# Sheet1.net
KiCad netlist of a schematic drawn in Altium Designer
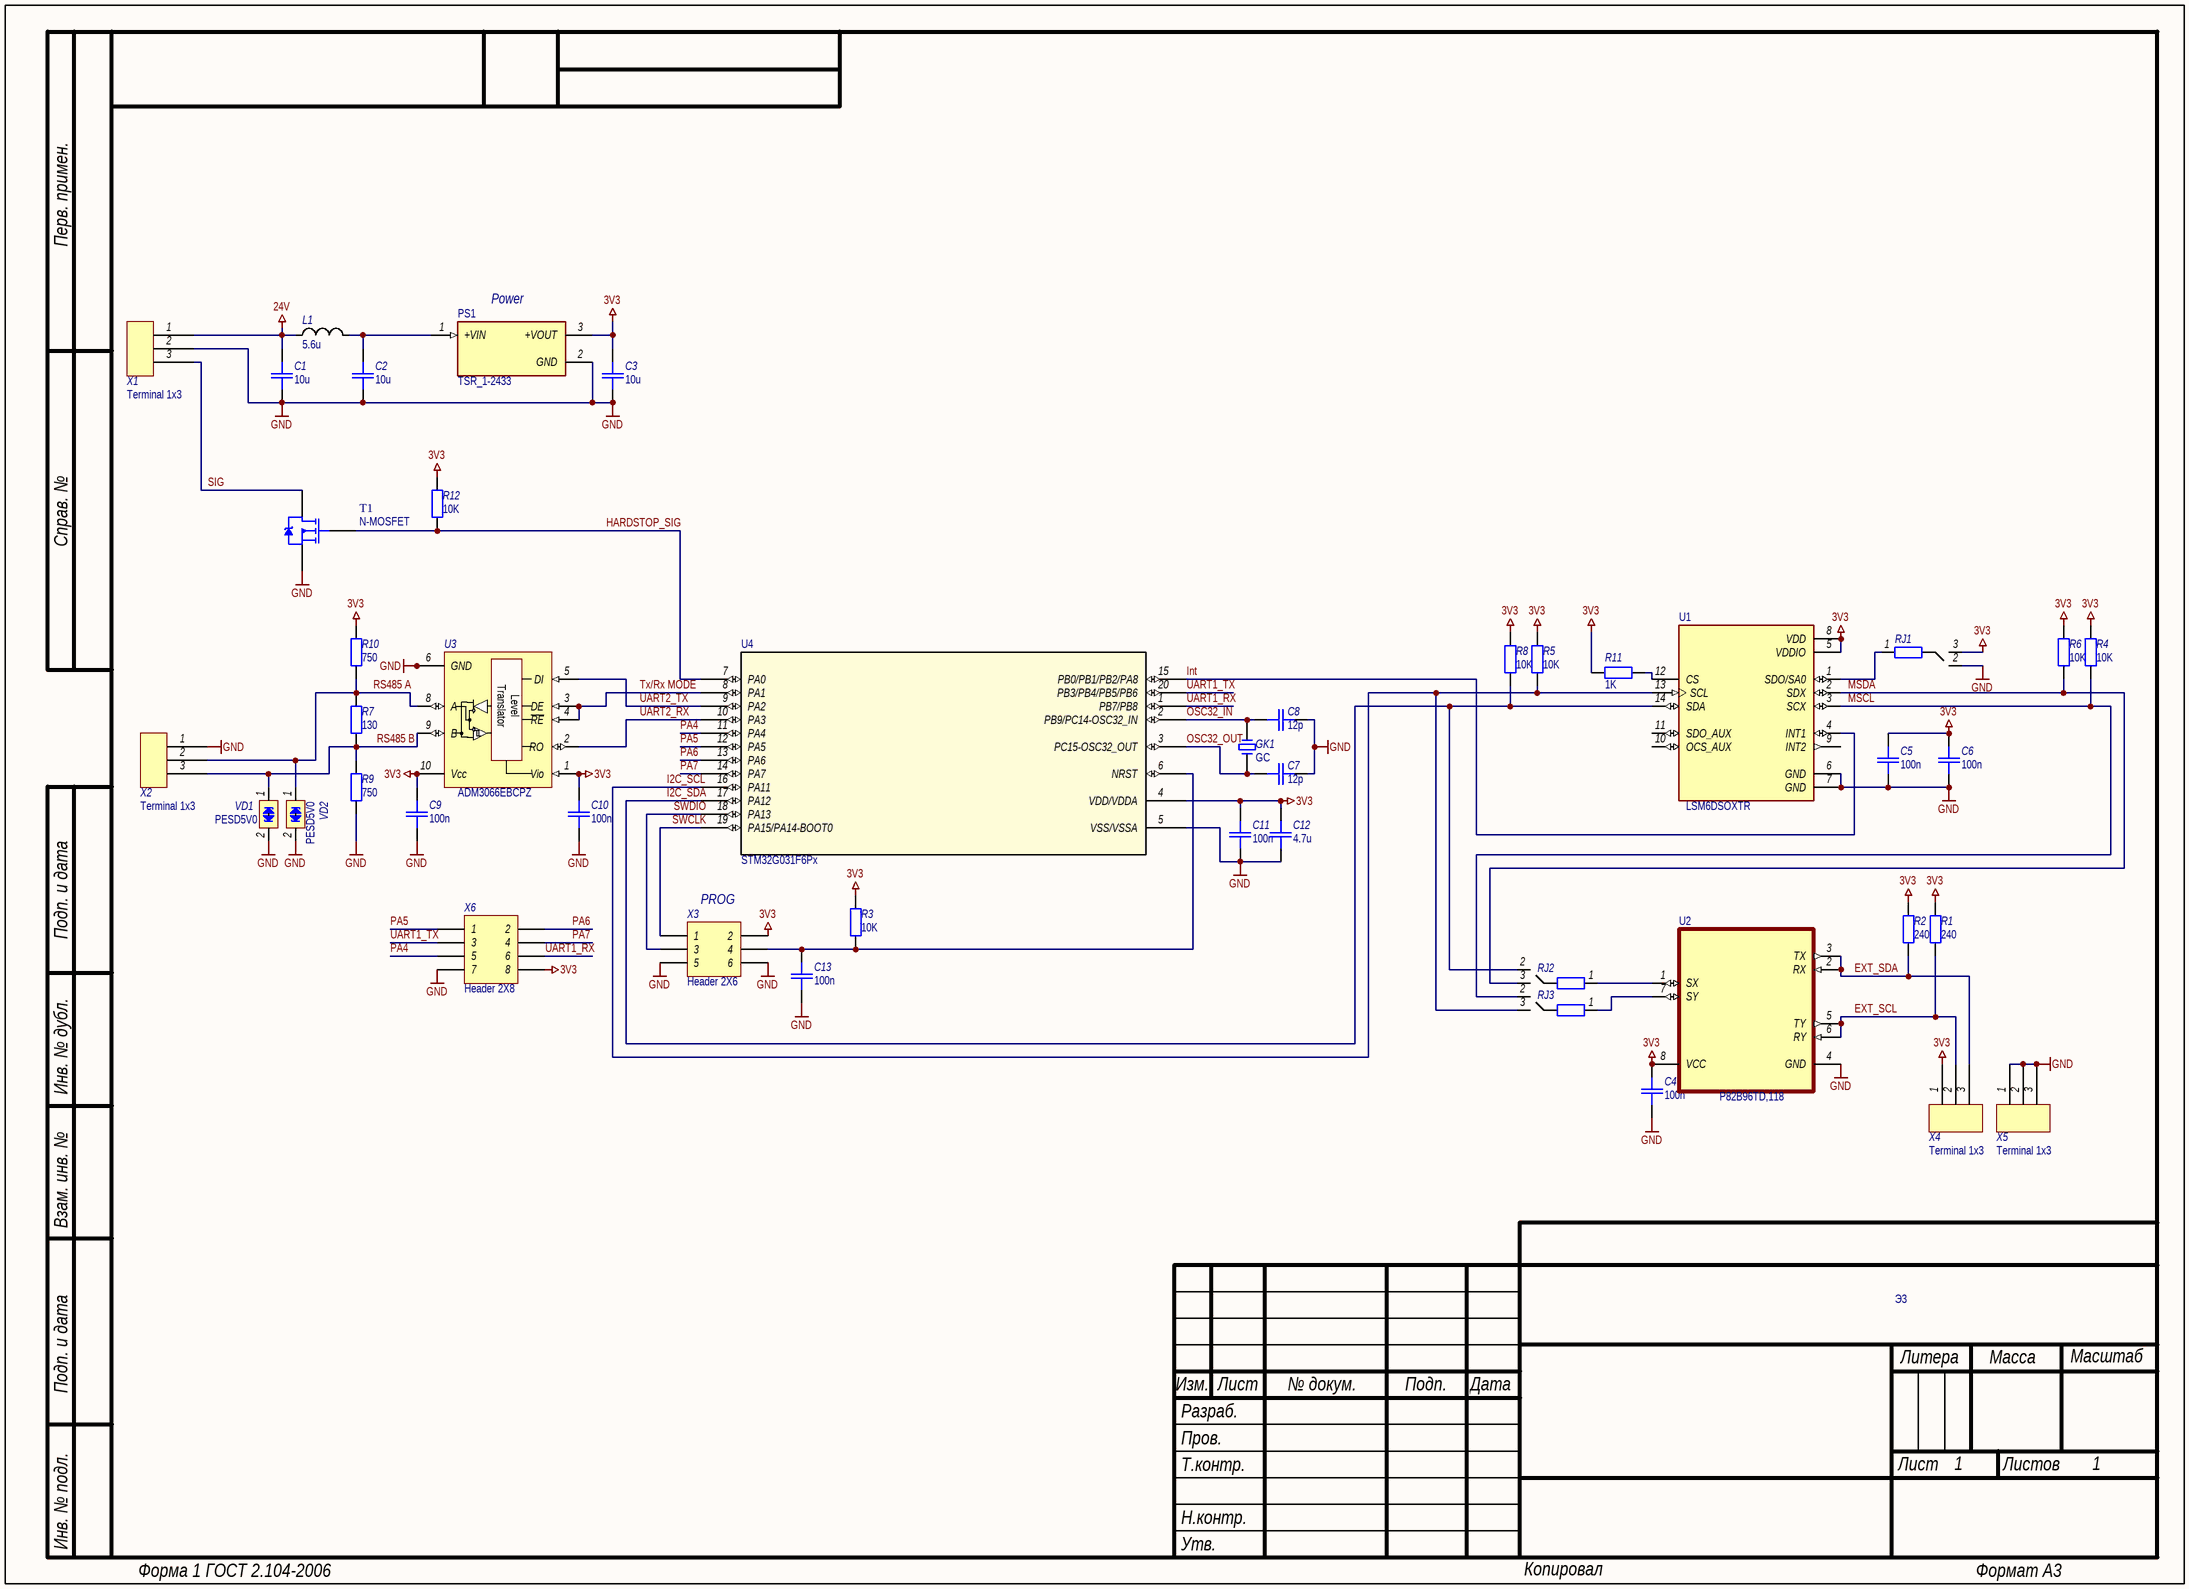
[diagram p0: Sheet1.SchDoc]

(export (version "E")
  (design (tool "Eeschema 10.0.6"))
  (components
    (comp (ref "C1")
      (value "10u")
      (footprint "SMD_C0805")
      (description "Capacitor")
      (fields (field (name "Comment") "K10-79"))
      (libsource (lib "Capacitor") (part "Capacitor"))
    )
    (comp (ref "C2")
      (value "10u")
      (footprint "SMD_C0805")
      (description "Capacitor")
      (fields (field (name "Comment") "K10-79"))
      (libsource (lib "Capacitor") (part "Capacitor"))
    )
    (comp (ref "C3")
      (value "10u")
      (footprint "SMD_C0805")
      (description "Capacitor")
      (fields (field (name "Comment") "K10-79"))
      (libsource (lib "Capacitor") (part "Capacitor"))
    )
    (comp (ref "C4")
      (value "100n")
      (footprint "SMD_C0805")
      (description "Capacitor")
      (fields (field (name "Comment") "K10-79"))
      (libsource (lib "Capacitor") (part "Capacitor"))
    )
    (comp (ref "C5")
      (value "100n")
      (footprint "SMD_C0805")
      (description "Capacitor")
      (fields (field (name "Comment") "K10-79"))
      (libsource (lib "Capacitor") (part "Capacitor"))
    )
    (comp (ref "C6")
      (value "100n")
      (footprint "SMD_C0805")
      (description "Capacitor")
      (fields (field (name "Comment") "K10-79"))
      (libsource (lib "Capacitor") (part "Capacitor"))
    )
    (comp (ref "C7")
      (value "12p")
      (footprint "SMD_C0805")
      (description "Capacitor")
      (fields (field (name "Comment") "K10-79"))
      (libsource (lib "Capacitor") (part "Capacitor"))
    )
    (comp (ref "C8")
      (value "12p")
      (footprint "SMD_C0805")
      (description "Capacitor")
      (fields (field (name "Comment") "K10-79"))
      (libsource (lib "Capacitor") (part "Capacitor"))
    )
    (comp (ref "C9")
      (value "100n")
      (footprint "SMD_C0805")
      (description "Capacitor")
      (fields (field (name "Comment") "K10-79"))
      (libsource (lib "Capacitor") (part "Capacitor"))
    )
    (comp (ref "C10")
      (value "100n")
      (footprint "SMD_C0805")
      (description "Capacitor")
      (fields (field (name "Comment") "K10-79"))
      (libsource (lib "Capacitor") (part "Capacitor"))
    )
    (comp (ref "C11")
      (value "100n")
      (footprint "SMD_C0805")
      (description "Capacitor")
      (fields (field (name "Comment") "K10-79"))
      (libsource (lib "Capacitor") (part "Capacitor"))
    )
    (comp (ref "C12")
      (value "4.7u")
      (footprint "SMD_C0805")
      (description "Capacitor")
      (fields (field (name "Comment") "K10-79"))
      (libsource (lib "Capacitor") (part "Capacitor"))
    )
    (comp (ref "C13")
      (value "100n")
      (footprint "SMD_C0805")
      (description "Capacitor")
      (fields (field (name "Comment") "K10-79"))
      (libsource (lib "Capacitor") (part "Capacitor"))
    )
    (comp (ref "GK1")
      (value "32.768k")
      (footprint "DT-38T")
      (description "Generic 2-Pin Crystal Oscillator")
      (fields (field (name "НАИМЕНОВАНИЕ") "GC"))
      (libsource (lib "Oscillator") (part "Crystal_Generic"))
    )
    (comp (ref "L1")
      (value "5.6u")
      (footprint "SMD_0805")
      (description "Inductor")
      (libsource (lib "Inductor") (part "Inductor"))
    )
    (comp (ref "PS1")
      (value "TSR_1-2433")
      (footprint "CONV_TSR_1-2433")
      (description "1 Amp POL switching regulator, 4.6 to -36 VDC input, pos.-pos. circuit, LM78 compatible, SIP-3")
      (fields (field (name "MP") "TSR 1-2433") (field (name "MF") "Traco Power"))
      (libsource (lib "TSR_1-2433") (part "TSR_1-2433"))
    )
    (comp (ref "R1")
      (value "240")
      (footprint "SMD_0805")
      (description "Resistor")
      (fields (field (name "Comment") "OSM R1-8"))
      (libsource (lib "Resistor") (part "Resistor"))
    )
    (comp (ref "R2")
      (value "240")
      (footprint "SMD_0805")
      (description "Resistor")
      (fields (field (name "Comment") "OSM R1-8"))
      (libsource (lib "Resistor") (part "Resistor"))
    )
    (comp (ref "R3")
      (value "10K")
      (footprint "SMD_0805")
      (description "Resistor")
      (fields (field (name "Comment") "OSM R1-8"))
      (libsource (lib "Resistor") (part "Resistor"))
    )
    (comp (ref "R4")
      (value "10K")
      (footprint "SMD_0805")
      (description "Resistor")
      (fields (field (name "Comment") "OSM R1-8"))
      (libsource (lib "Resistor") (part "Resistor"))
    )
    (comp (ref "R5")
      (value "10K")
      (footprint "SMD_0805")
      (description "Resistor")
      (fields (field (name "Comment") "OSM R1-8"))
      (libsource (lib "Resistor") (part "Resistor"))
    )
    (comp (ref "R6")
      (value "10K")
      (footprint "SMD_0805")
      (description "Resistor")
      (fields (field (name "Comment") "OSM R1-8"))
      (libsource (lib "Resistor") (part "Resistor"))
    )
    (comp (ref "R7")
      (value "130")
      (footprint "SMD_0805")
      (description "Resistor")
      (fields (field (name "Comment") "OSM R1-8"))
      (libsource (lib "") (part "Resistor_2"))
    )
    (comp (ref "R8")
      (value "10K")
      (footprint "SMD_0805")
      (description "Resistor")
      (fields (field (name "Comment") "OSM R1-8"))
      (libsource (lib "Resistor") (part "Resistor"))
    )
    (comp (ref "R9")
      (value "750")
      (footprint "SMD_0805")
      (description "Resistor")
      (fields (field (name "Comment") "OSM R1-8"))
      (libsource (lib "Resistor") (part "Resistor"))
    )
    (comp (ref "R10")
      (value "750")
      (footprint "SMD_0805")
      (description "Resistor")
      (fields (field (name "Comment") "OSM R1-8"))
      (libsource (lib "") (part "Resistor_2"))
    )
    (comp (ref "R11")
      (value "1K")
      (footprint "SMD_0805")
      (description "Resistor")
      (fields (field (name "Comment") "OSM R1-8"))
      (libsource (lib "") (part "Resistor_1"))
    )
    (comp (ref "R12")
      (value "10K")
      (footprint "SMD_0805")
      (description "Resistor")
      (fields (field (name "Comment") "OSM R1-8"))
      (libsource (lib "") (part "Resistor_2"))
    )
    (comp (ref "RJ1")
      (value "OSM R1-8")
      (footprint "SMD_JMP_0805")
      (description "Resistor-Jumper")
      (libsource (lib "Passive") (part "Resistor_Jamper"))
    )
    (comp (ref "RJ2")
      (value "OSM R1-8")
      (footprint "SMD_JMP_0805")
      (description "Resistor-Jumper")
      (libsource (lib "") (part "Resistor_Jamper_1"))
    )
    (comp (ref "RJ3")
      (value "OSM R1-8")
      (footprint "SMD_JMP_0805")
      (description "Resistor-Jumper")
      (libsource (lib "") (part "Resistor_Jamper_1"))
    )
    (comp (ref "T1")
      (value "N-MOSFET")
      (footprint "SOT-23")
      (description "N channel Generic MosFET")
      (fields (field (name "НАИМЕНОВАНИЕ") "N-MOSFET"))
      (libsource (lib "Transistor") (part "N-MOSFET"))
    )
    (comp (ref "U1")
      (value "LSM6DSOXTR")
      (footprint "PQFN50P250X300X86-14N")
      (description "Accelerometer, Gyroscope, 6 Axis Sensor IÂ²C, SPI Output")
      (fields (field (name "MF") "STMicroelectronics"))
      (libsource (lib "LSM6DSOXTR") (part "LSM6DSOXTR"))
    )
    (comp (ref "U2")
      (value "P82B96TD,118")
      (footprint "SOIC127P600X175-8N")
      (description "Dual bidirectional bus buffer")
      (fields (field (name "MP") "P82B96TD-118"))
      (libsource (lib "P82B96TD_118") (part "P82B96TD,118"))
    )
    (comp (ref "U3")
      (value "ADM3066EBCPZ")
      (footprint "LFCSP-10_3x3")
      (description "3.0 V to 5.5 V, ±12 kV IEC ESD Protected, 500 kbps/50 Mbps RS-485 Transceiver")
      (libsource (lib "Transceiver") (part "ADM3066E"))
    )
    (comp (ref "U4")
      (value "STM32G031F6Px")
      (footprint "TSSOP20")
      (fields
        (field (name "MANUFACTURER_PART_NUMBER") "stm32g0_tssop20_t1")
        (field (name "COPYRIGHT") "Copyright (C) 2018 Accelerated Designs. All rights reserved")
      )
      (libsource (lib "ST Microelectronics STM32 G0") (part "STM32G031F6Px"))
    )
    (comp (ref "VD1")
      (value "PESD5V0")
      (footprint "SOD-323")
      (description "Low capacitance bidirectional ESD protection diodes")
      (libsource (lib "Diod") (part "PESDxL1BA"))
    )
    (comp (ref "VD2")
      (value "PESD5V0")
      (footprint "SOD-323")
      (description "Low capacitance bidirectional ESD protection diodes")
      (libsource (lib "Diod") (part "PESDxL1BA"))
    )
    (comp (ref "X1")
      (value "Terminal 1x3")
      (footprint "DXMG-3WAY")
      (libsource (lib "") (part "Terminal 1x3_1"))
    )
    (comp (ref "X2")
      (value "Terminal 1x3")
      (footprint "DXMG-3WAY")
      (libsource (lib "") (part "Terminal 1x3_1"))
    )
    (comp (ref "X3")
      (value "Header 2X6")
      (footprint "PLD2-6")
      (description "Header, 6-Pin, Dual row")
      (fields (field (name "НАИМЕНОВАНИЕ") "Header 2X6"))
      (libsource (lib "Connector") (part "Header 2X6"))
    )
    (comp (ref "X4")
      (value "Terminal 1x3")
      (footprint "DxMG 3WAY:DXMG-3WAY")
      (libsource (lib "DxMG 3WAY") (part "Terminal 1x3"))
    )
    (comp (ref "X5")
      (value "Terminal 1x3")
      (footprint "DxMG 3WAY:DXMG-3WAY")
      (libsource (lib "DxMG 3WAY") (part "Terminal 1x3"))
    )
    (comp (ref "X6")
      (value "Header 2X8")
      (footprint "PBD-8")
      (description "Header, 8-Pin, Dual row")
      (fields (field (name "НАИМЕНОВАНИЕ") "Header 2X8"))
      (libsource (lib "Connector") (part "Header 2X8"))
    )
  )
  (nets
    (net (code "1") (name "/EXT_SCL") (class "Default")
      (node (ref "R1") (pin "1") (pinfunction "1_1") (pintype "passive"))
      (node (ref "U2") (pin "5") (pinfunction "TY_5") (pintype "output"))
      (node (ref "U2") (pin "6") (pinfunction "RY_6") (pintype "input"))
      (node (ref "X4") (pin "2") (pinfunction "2_2") (pintype "passive"))
    )
    (net (code "2") (name "/EXT_SDA") (class "Default")
      (node (ref "R2") (pin "1") (pinfunction "1_1") (pintype "passive"))
      (node (ref "U2") (pin "2") (pinfunction "RX_2") (pintype "input"))
      (node (ref "U2") (pin "3") (pinfunction "TX_3") (pintype "output"))
      (node (ref "X4") (pin "3") (pinfunction "3_3") (pintype "passive"))
    )
    (net (code "3") (name "/HARDSTOP_SIG") (class "Default")
      (node (ref "R12") (pin "2") (pinfunction "2_2") (pintype "passive"))
      (node (ref "T1") (pin "G") (pinfunction "GATE_G") (pintype "passive"))
      (node (ref "U4") (pin "7") (pinfunction "PA0_7") (pintype "bidirectional"))
    )
    (net (code "4") (name "/I2C_SCL") (class "Default")
      (node (ref "R5") (pin "1") (pinfunction "1_1") (pintype "passive"))
      (node (ref "RJ3") (pin "3") (pintype "passive"))
      (node (ref "U1") (pin "13") (pinfunction "SCL_13") (pintype "input"))
      (node (ref "U4") (pin "16") (pinfunction "PA11_16") (pintype "bidirectional"))
    )
    (net (code "5") (name "/I2C_SDA") (class "Default")
      (node (ref "R8") (pin "1") (pinfunction "1_1") (pintype "passive"))
      (node (ref "RJ2") (pin "2") (pintype "passive"))
      (node (ref "U1") (pin "14") (pinfunction "SDA_14") (pintype "bidirectional"))
      (node (ref "U4") (pin "17") (pinfunction "PA12_17") (pintype "bidirectional"))
    )
    (net (code "6") (name "/Int") (class "Default")
      (node (ref "U1") (pin "4") (pinfunction "INT1_4") (pintype "bidirectional"))
      (node (ref "U4") (pin "15") (pinfunction "PB0/PB1/PB2/PA8_15") (pintype "bidirectional"))
    )
    (net (code "7") (name "/MSCL") (class "Default")
      (node (ref "R4") (pin "1") (pinfunction "1_1") (pintype "passive"))
      (node (ref "RJ3") (pin "2") (pintype "passive"))
      (node (ref "U1") (pin "3") (pinfunction "SCX_3") (pintype "bidirectional"))
    )
    (net (code "8") (name "/MSDA") (class "Default")
      (node (ref "R6") (pin "1") (pinfunction "1_1") (pintype "passive"))
      (node (ref "RJ2") (pin "3") (pintype "passive"))
      (node (ref "U1") (pin "2") (pinfunction "SDX_2") (pintype "bidirectional"))
    )
    (net (code "9") (name "/OSC32_IN") (class "Default")
      (node (ref "C8") (pin "2") (pinfunction "2_2") (pintype "passive"))
      (node (ref "GK1") (pin "1") (pinfunction "1_1") (pintype "passive"))
      (node (ref "U4") (pin "2") (pinfunction "PB9/PC14-OSC32_IN_2") (pintype "bidirectional"))
    )
    (net (code "10") (name "/OSC32_OUT") (class "Default")
      (node (ref "C7") (pin "2") (pinfunction "2_2") (pintype "passive"))
      (node (ref "GK1") (pin "2") (pinfunction "2_2") (pintype "passive"))
      (node (ref "U4") (pin "3") (pinfunction "PC15-OSC32_OUT_3") (pintype "bidirectional"))
    )
    (net (code "11") (name "/PA4") (class "Default")
      (node (ref "U4") (pin "11") (pinfunction "PA4_11") (pintype "bidirectional"))
      (node (ref "X6") (pin "5") (pinfunction "5_5") (pintype "passive"))
    )
    (net (code "12") (name "/PA5") (class "Default")
      (node (ref "U4") (pin "12") (pinfunction "PA5_12") (pintype "bidirectional"))
      (node (ref "X6") (pin "1") (pinfunction "1_1") (pintype "passive"))
    )
    (net (code "13") (name "/PA6") (class "Default")
      (node (ref "U4") (pin "13") (pinfunction "PA6_13") (pintype "bidirectional"))
      (node (ref "X6") (pin "2") (pinfunction "2_2") (pintype "passive"))
    )
    (net (code "14") (name "/PA7") (class "Default")
      (node (ref "U4") (pin "14") (pinfunction "PA7_14") (pintype "bidirectional"))
      (node (ref "X6") (pin "4") (pinfunction "4_4") (pintype "passive"))
    )
    (net (code "15") (name "/RS485 A") (class "Default")
      (node (ref "R10") (pin "2") (pinfunction "2_2") (pintype "passive"))
      (node (ref "R7") (pin "1") (pinfunction "1_1") (pintype "passive"))
      (node (ref "U3") (pin "8") (pinfunction "A_8") (pintype "bidirectional"))
      (node (ref "VD2") (pin "1") (pinfunction "cathode_1_1") (pintype "passive"))
      (node (ref "X2") (pin "2") (pinfunction "2_2") (pintype "passive"))
    )
    (net (code "16") (name "/RS485 B") (class "Default")
      (node (ref "R7") (pin "2") (pinfunction "2_2") (pintype "passive"))
      (node (ref "R9") (pin "2") (pinfunction "2_2") (pintype "passive"))
      (node (ref "U3") (pin "9") (pinfunction "B_9") (pintype "bidirectional"))
      (node (ref "VD1") (pin "1") (pinfunction "cathode_1_1") (pintype "passive"))
      (node (ref "X2") (pin "3") (pinfunction "3_3") (pintype "passive"))
    )
    (net (code "17") (name "/SIG") (class "Default")
      (node (ref "T1") (pin "D") (pinfunction "DRAIN_D") (pintype "passive"))
      (node (ref "X1") (pin "3") (pinfunction "3_3") (pintype "passive"))
    )
    (net (code "18") (name "/SWCLK") (class "Default")
      (node (ref "U4") (pin "19") (pinfunction "PA15/PA14-BOOT0_19") (pintype "bidirectional"))
      (node (ref "X3") (pin "1") (pinfunction "1_1") (pintype "passive"))
    )
    (net (code "19") (name "/SWDIO") (class "Default")
      (node (ref "U4") (pin "18") (pinfunction "PA13_18") (pintype "bidirectional"))
      (node (ref "X3") (pin "3") (pinfunction "3_3") (pintype "passive"))
    )
    (net (code "20") (name "/Tx{slash}Rx MODE") (class "Default")
      (node (ref "U3") (pin "3") (pinfunction "DE_3") (pintype "input"))
      (node (ref "U3") (pin "4") (pinfunction "~{RE}_4") (pintype "input"))
      (node (ref "U4") (pin "8") (pinfunction "PA1_8") (pintype "bidirectional"))
    )
    (net (code "21") (name "/UART1_RX") (class "Default")
      (node (ref "U4") (pin "1") (pinfunction "PB7/PB8_1") (pintype "bidirectional"))
      (node (ref "X6") (pin "6") (pinfunction "6_6") (pintype "passive"))
    )
    (net (code "22") (name "/UART1_TX") (class "Default")
      (node (ref "U4") (pin "20") (pinfunction "PB3/PB4/PB5/PB6_20") (pintype "bidirectional"))
      (node (ref "X6") (pin "3") (pinfunction "3_3") (pintype "passive"))
    )
    (net (code "23") (name "/UART2_RX") (class "Default")
      (node (ref "U3") (pin "2") (pinfunction "RO_2") (pintype "bidirectional"))
      (node (ref "U4") (pin "10") (pinfunction "PA3_10") (pintype "bidirectional"))
    )
    (net (code "24") (name "/UART2_TX") (class "Default")
      (node (ref "U3") (pin "5") (pinfunction "DI_5") (pintype "input"))
      (node (ref "U4") (pin "9") (pinfunction "PA2_9") (pintype "bidirectional"))
    )
    (net (code "25") (name "3V3") (class "Default")
      (node (ref "C10") (pin "2") (pinfunction "2_2") (pintype "passive"))
      (node (ref "C11") (pin "1") (pinfunction "1_1") (pintype "passive"))
      (node (ref "C12") (pin "1") (pinfunction "1_1") (pintype "passive"))
      (node (ref "C3") (pin "2") (pinfunction "2_2") (pintype "passive"))
      (node (ref "C4") (pin "2") (pinfunction "2_2") (pintype "passive"))
      (node (ref "C5") (pin "1") (pinfunction "1_1") (pintype "passive"))
      (node (ref "C6") (pin "1") (pinfunction "1_1") (pintype "passive"))
      (node (ref "C9") (pin "2") (pinfunction "2_2") (pintype "passive"))
      (node (ref "PS1") (pin "3") (pinfunction "+VOUT_3") (pintype "power_in"))
      (node (ref "R1") (pin "2") (pinfunction "2_2") (pintype "passive"))
      (node (ref "R10") (pin "1") (pinfunction "1_1") (pintype "passive"))
      (node (ref "R11") (pin "2") (pinfunction "2_2") (pintype "passive"))
      (node (ref "R12") (pin "1") (pinfunction "1_1") (pintype "passive"))
      (node (ref "R2") (pin "2") (pinfunction "2_2") (pintype "passive"))
      (node (ref "R3") (pin "2") (pinfunction "2_2") (pintype "passive"))
      (node (ref "R4") (pin "2") (pinfunction "2_2") (pintype "passive"))
      (node (ref "R5") (pin "2") (pinfunction "2_2") (pintype "passive"))
      (node (ref "R6") (pin "2") (pinfunction "2_2") (pintype "passive"))
      (node (ref "R8") (pin "2") (pinfunction "2_2") (pintype "passive"))
      (node (ref "RJ1") (pin "3") (pintype "passive"))
      (node (ref "U1") (pin "5") (pinfunction "VDDIO_5") (pintype "power_in"))
      (node (ref "U1") (pin "8") (pinfunction "VDD_8") (pintype "power_in"))
      (node (ref "U2") (pin "8") (pinfunction "VCC_8") (pintype "power_in"))
      (node (ref "U3") (pin "1") (pinfunction "Vio_1") (pintype "input"))
      (node (ref "U3") (pin "10") (pinfunction "Vcc_10") (pintype "power_in"))
      (node (ref "U4") (pin "4") (pinfunction "VDD/VDDA_4") (pintype "power_in"))
      (node (ref "X3") (pin "2") (pinfunction "2_2") (pintype "passive"))
      (node (ref "X4") (pin "1") (pinfunction "1_1") (pintype "passive"))
      (node (ref "X6") (pin "8") (pinfunction "8_8") (pintype "passive"))
    )
    (net (code "26") (name "24V") (class "Default")
      (node (ref "C1") (pin "2") (pinfunction "2_2") (pintype "passive"))
      (node (ref "L1") (pin "1") (pinfunction "1_1") (pintype "passive"))
      (node (ref "X1") (pin "1") (pinfunction "1_1") (pintype "passive"))
    )
    (net (code "27") (name "GND") (class "Default")
      (node (ref "C1") (pin "1") (pinfunction "1_1") (pintype "passive"))
      (node (ref "C10") (pin "1") (pinfunction "1_1") (pintype "passive"))
      (node (ref "C11") (pin "2") (pinfunction "2_2") (pintype "passive"))
      (node (ref "C12") (pin "2") (pinfunction "2_2") (pintype "passive"))
      (node (ref "C13") (pin "2") (pinfunction "2_2") (pintype "passive"))
      (node (ref "C2") (pin "1") (pinfunction "1_1") (pintype "passive"))
      (node (ref "C3") (pin "1") (pinfunction "1_1") (pintype "passive"))
      (node (ref "C4") (pin "1") (pinfunction "1_1") (pintype "passive"))
      (node (ref "C5") (pin "2") (pinfunction "2_2") (pintype "passive"))
      (node (ref "C6") (pin "2") (pinfunction "2_2") (pintype "passive"))
      (node (ref "C7") (pin "1") (pinfunction "1_1") (pintype "passive"))
      (node (ref "C8") (pin "1") (pinfunction "1_1") (pintype "passive"))
      (node (ref "C9") (pin "1") (pinfunction "1_1") (pintype "passive"))
      (node (ref "PS1") (pin "2") (pinfunction "GND_2") (pintype "power_in"))
      (node (ref "R9") (pin "1") (pinfunction "1_1") (pintype "passive"))
      (node (ref "RJ1") (pin "2") (pintype "passive"))
      (node (ref "T1") (pin "S") (pinfunction "SOURCE_S") (pintype "passive"))
      (node (ref "U1") (pin "6") (pinfunction "GND_6") (pintype "power_in"))
      (node (ref "U1") (pin "7") (pinfunction "GND_7") (pintype "power_in"))
      (node (ref "U2") (pin "4") (pinfunction "GND_4") (pintype "passive"))
      (node (ref "U3") (pin "11") (pinfunction "GND_11") (pintype "power_in"))
      (node (ref "U3") (pin "6") (pinfunction "GND_6") (pintype "power_in"))
      (node (ref "U4") (pin "5") (pinfunction "VSS/VSSA_5") (pintype "power_in"))
      (node (ref "VD1") (pin "2") (pinfunction "cathode_2_2") (pintype "passive"))
      (node (ref "VD2") (pin "2") (pinfunction "cathode_2_2") (pintype "passive"))
      (node (ref "X1") (pin "2") (pinfunction "2_2") (pintype "passive"))
      (node (ref "X2") (pin "1") (pinfunction "1_1") (pintype "passive"))
      (node (ref "X3") (pin "5") (pinfunction "5_5") (pintype "passive"))
      (node (ref "X3") (pin "6") (pinfunction "6_6") (pintype "passive"))
      (node (ref "X5") (pin "1") (pinfunction "1_1") (pintype "passive"))
      (node (ref "X5") (pin "2") (pinfunction "2_2") (pintype "passive"))
      (node (ref "X5") (pin "3") (pinfunction "3_3") (pintype "passive"))
      (node (ref "X6") (pin "7") (pinfunction "7_7") (pintype "passive"))
    )
    (net (code "28") (name "Net-(PS1-+VIN)") (class "Default")
      (node (ref "C2") (pin "2") (pinfunction "2_2") (pintype "passive"))
      (node (ref "L1") (pin "2") (pinfunction "2_2") (pintype "passive"))
      (node (ref "PS1") (pin "1") (pinfunction "+VIN_1") (pintype "input"))
    )
    (net (code "29") (name "Net-(U1-CS)") (class "Default")
      (node (ref "R11") (pin "1") (pinfunction "1_1") (pintype "passive"))
      (node (ref "U1") (pin "12") (pinfunction "CS_12") (pintype "passive"))
    )
    (net (code "30") (name "Net-(U1-SDO{slash}SA0)") (class "Default")
      (node (ref "RJ1") (pin "1") (pintype "passive"))
      (node (ref "U1") (pin "1") (pinfunction "SDO/SA0_1") (pintype "bidirectional"))
    )
    (net (code "31") (name "Net-(U2-SX)") (class "Default")
      (node (ref "RJ2") (pin "1") (pintype "passive"))
      (node (ref "U2") (pin "1") (pinfunction "SX_1") (pintype "bidirectional"))
    )
    (net (code "32") (name "Net-(U2-SY)") (class "Default")
      (node (ref "RJ3") (pin "1") (pintype "passive"))
      (node (ref "U2") (pin "7") (pinfunction "SY_7") (pintype "bidirectional"))
    )
    (net (code "33") (name "Net-(U4-NRST)") (class "Default")
      (node (ref "C13") (pin "1") (pinfunction "1_1") (pintype "passive"))
      (node (ref "R3") (pin "1") (pinfunction "1_1") (pintype "passive"))
      (node (ref "U4") (pin "6") (pinfunction "NRST_6") (pintype "bidirectional"))
      (node (ref "X3") (pin "4") (pinfunction "4_4") (pintype "passive"))
    )
    (net (code "34") (name "unconnected-(U1-INT2-Pad9)") (class "Default")
      (node (ref "U1") (pin "9") (pinfunction "INT2_9") (pintype "output"))
    )
    (net (code "35") (name "unconnected-(U1-OCS_AUX-Pad10)") (class "Default")
      (node (ref "U1") (pin "10") (pinfunction "OCS_AUX_10") (pintype "bidirectional"))
    )
    (net (code "36") (name "unconnected-(U1-SDO_AUX-Pad11)") (class "Default")
      (node (ref "U1") (pin "11") (pinfunction "SDO_AUX_11") (pintype "bidirectional"))
    )
  )
)
